# Tail_Lights.net
KiCad netlist of a schematic drawn in EAGLE
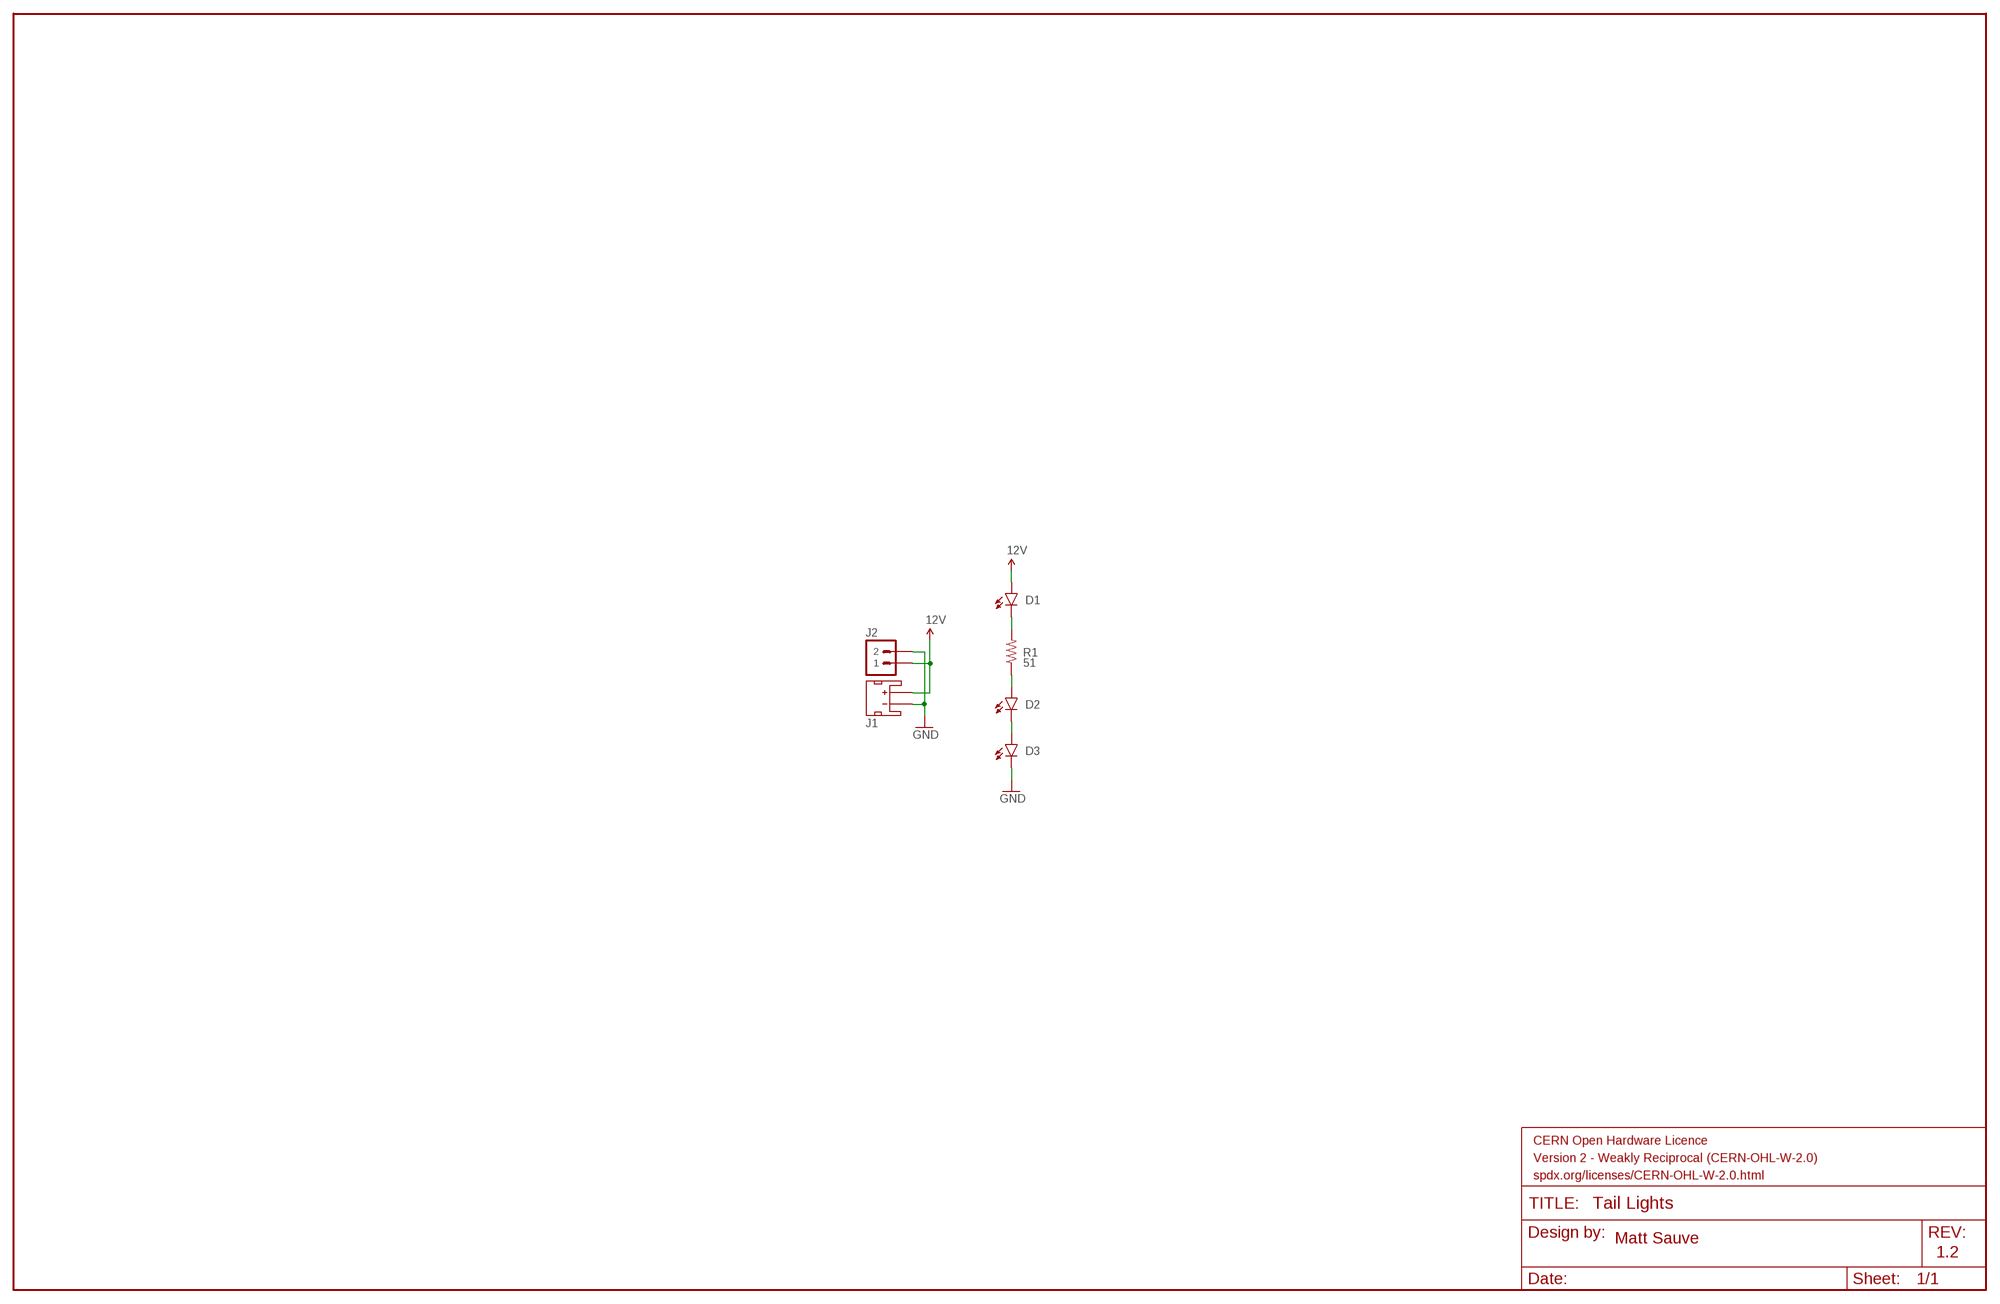
[diagram p0: schematic, sheet 1]

(export (version "E")
  (design (tool "Eeschema 10.0.6"))
  (components
    (comp (ref "D1")
      (value "RED_CREE_LED")
      (footprint "eagle-import:4-SMD")
      (libsource (lib "eagle-import") (part "RED_CREE_LED"))
    )
    (comp (ref "D2")
      (value "RED_CREE_LED")
      (footprint "eagle-import:4-SMD")
      (libsource (lib "eagle-import") (part "RED_CREE_LED"))
    )
    (comp (ref "D3")
      (value "RED_CREE_LED")
      (footprint "eagle-import:4-SMD")
      (libsource (lib "eagle-import") (part "RED_CREE_LED"))
    )
    (comp (ref "FRAME1")
      (value "FRAME-LEDGER_CERN_WEAK")
      (footprint "eagle-import:CERN_WEAK")
      (libsource (lib "eagle-import") (part "FRAME-LEDGER_CERN_WEAK"))
    )
    (comp (ref "J1")
      (value "JST_2MM_MALE")
      (footprint "eagle-import:JST-2-SMD")
      (libsource (lib "eagle-import") (part "JST_2MM_MALE"))
    )
    (comp (ref "J2")
      (value "JST_PH_2POS")
      (footprint "eagle-import:JST_PH_2POS")
      (libsource (lib "eagle-import") (part "JST_PH_2POS"))
    )
    (comp (ref "R1")
      (value "51")
      (footprint "eagle-import:R2512")
      (libsource (lib "eagle-import") (part "RESISTOR2512"))
    )
  )
  (nets
    (net (code "1") (name "12V") (class "Default")
      (node (ref "D1") (pin "P$1") (pinfunction "A_P$1") (pintype "passive"))
      (node (ref "D1") (pin "P$2") (pinfunction "A_P$2") (pintype "passive"))
      (node (ref "J1") (pin "2") (pinfunction "+_2") (pintype "bidirectional"))
      (node (ref "J2") (pin "1") (pinfunction "1_1") (pintype "passive"))
    )
    (net (code "2") (name "GND") (class "Default")
      (node (ref "D3") (pin "P$3") (pinfunction "C_P$3") (pintype "passive"))
      (node (ref "D3") (pin "P$4") (pinfunction "C_P$4") (pintype "passive"))
      (node (ref "J1") (pin "1") (pinfunction "-_1") (pintype "bidirectional"))
      (node (ref "J2") (pin "2") (pinfunction "2_2") (pintype "passive"))
    )
    (net (code "3") (name "Net-(D1-C-PadP$3)") (class "Default")
      (node (ref "D1") (pin "P$3") (pinfunction "C_P$3") (pintype "passive"))
      (node (ref "D1") (pin "P$4") (pinfunction "C_P$4") (pintype "passive"))
      (node (ref "R1") (pin "2") (pinfunction "2_2") (pintype "passive"))
    )
    (net (code "4") (name "Net-(D2-A-PadP$1)") (class "Default")
      (node (ref "D2") (pin "P$1") (pinfunction "A_P$1") (pintype "passive"))
      (node (ref "D2") (pin "P$2") (pinfunction "A_P$2") (pintype "passive"))
      (node (ref "R1") (pin "1") (pinfunction "1_1") (pintype "passive"))
    )
    (net (code "5") (name "Net-(D2-C-PadP$3)") (class "Default")
      (node (ref "D2") (pin "P$3") (pinfunction "C_P$3") (pintype "passive"))
      (node (ref "D2") (pin "P$4") (pinfunction "C_P$4") (pintype "passive"))
      (node (ref "D3") (pin "P$1") (pinfunction "A_P$1") (pintype "passive"))
      (node (ref "D3") (pin "P$2") (pinfunction "A_P$2") (pintype "passive"))
    )
    (net (code "6") (name "unconnected-(J1-PAD1-PadNC1)") (class "Default")
      (node (ref "J1") (pin "NC1") (pinfunction "PAD1_NC1") (pintype "bidirectional"))
    )
    (net (code "7") (name "unconnected-(J1-PAD2-PadNC2)") (class "Default")
      (node (ref "J1") (pin "NC2") (pinfunction "PAD2_NC2") (pintype "bidirectional"))
    )
  )
)
